# sensact_eagle_2_0g.net
KiCad netlist of a schematic drawn in EAGLE
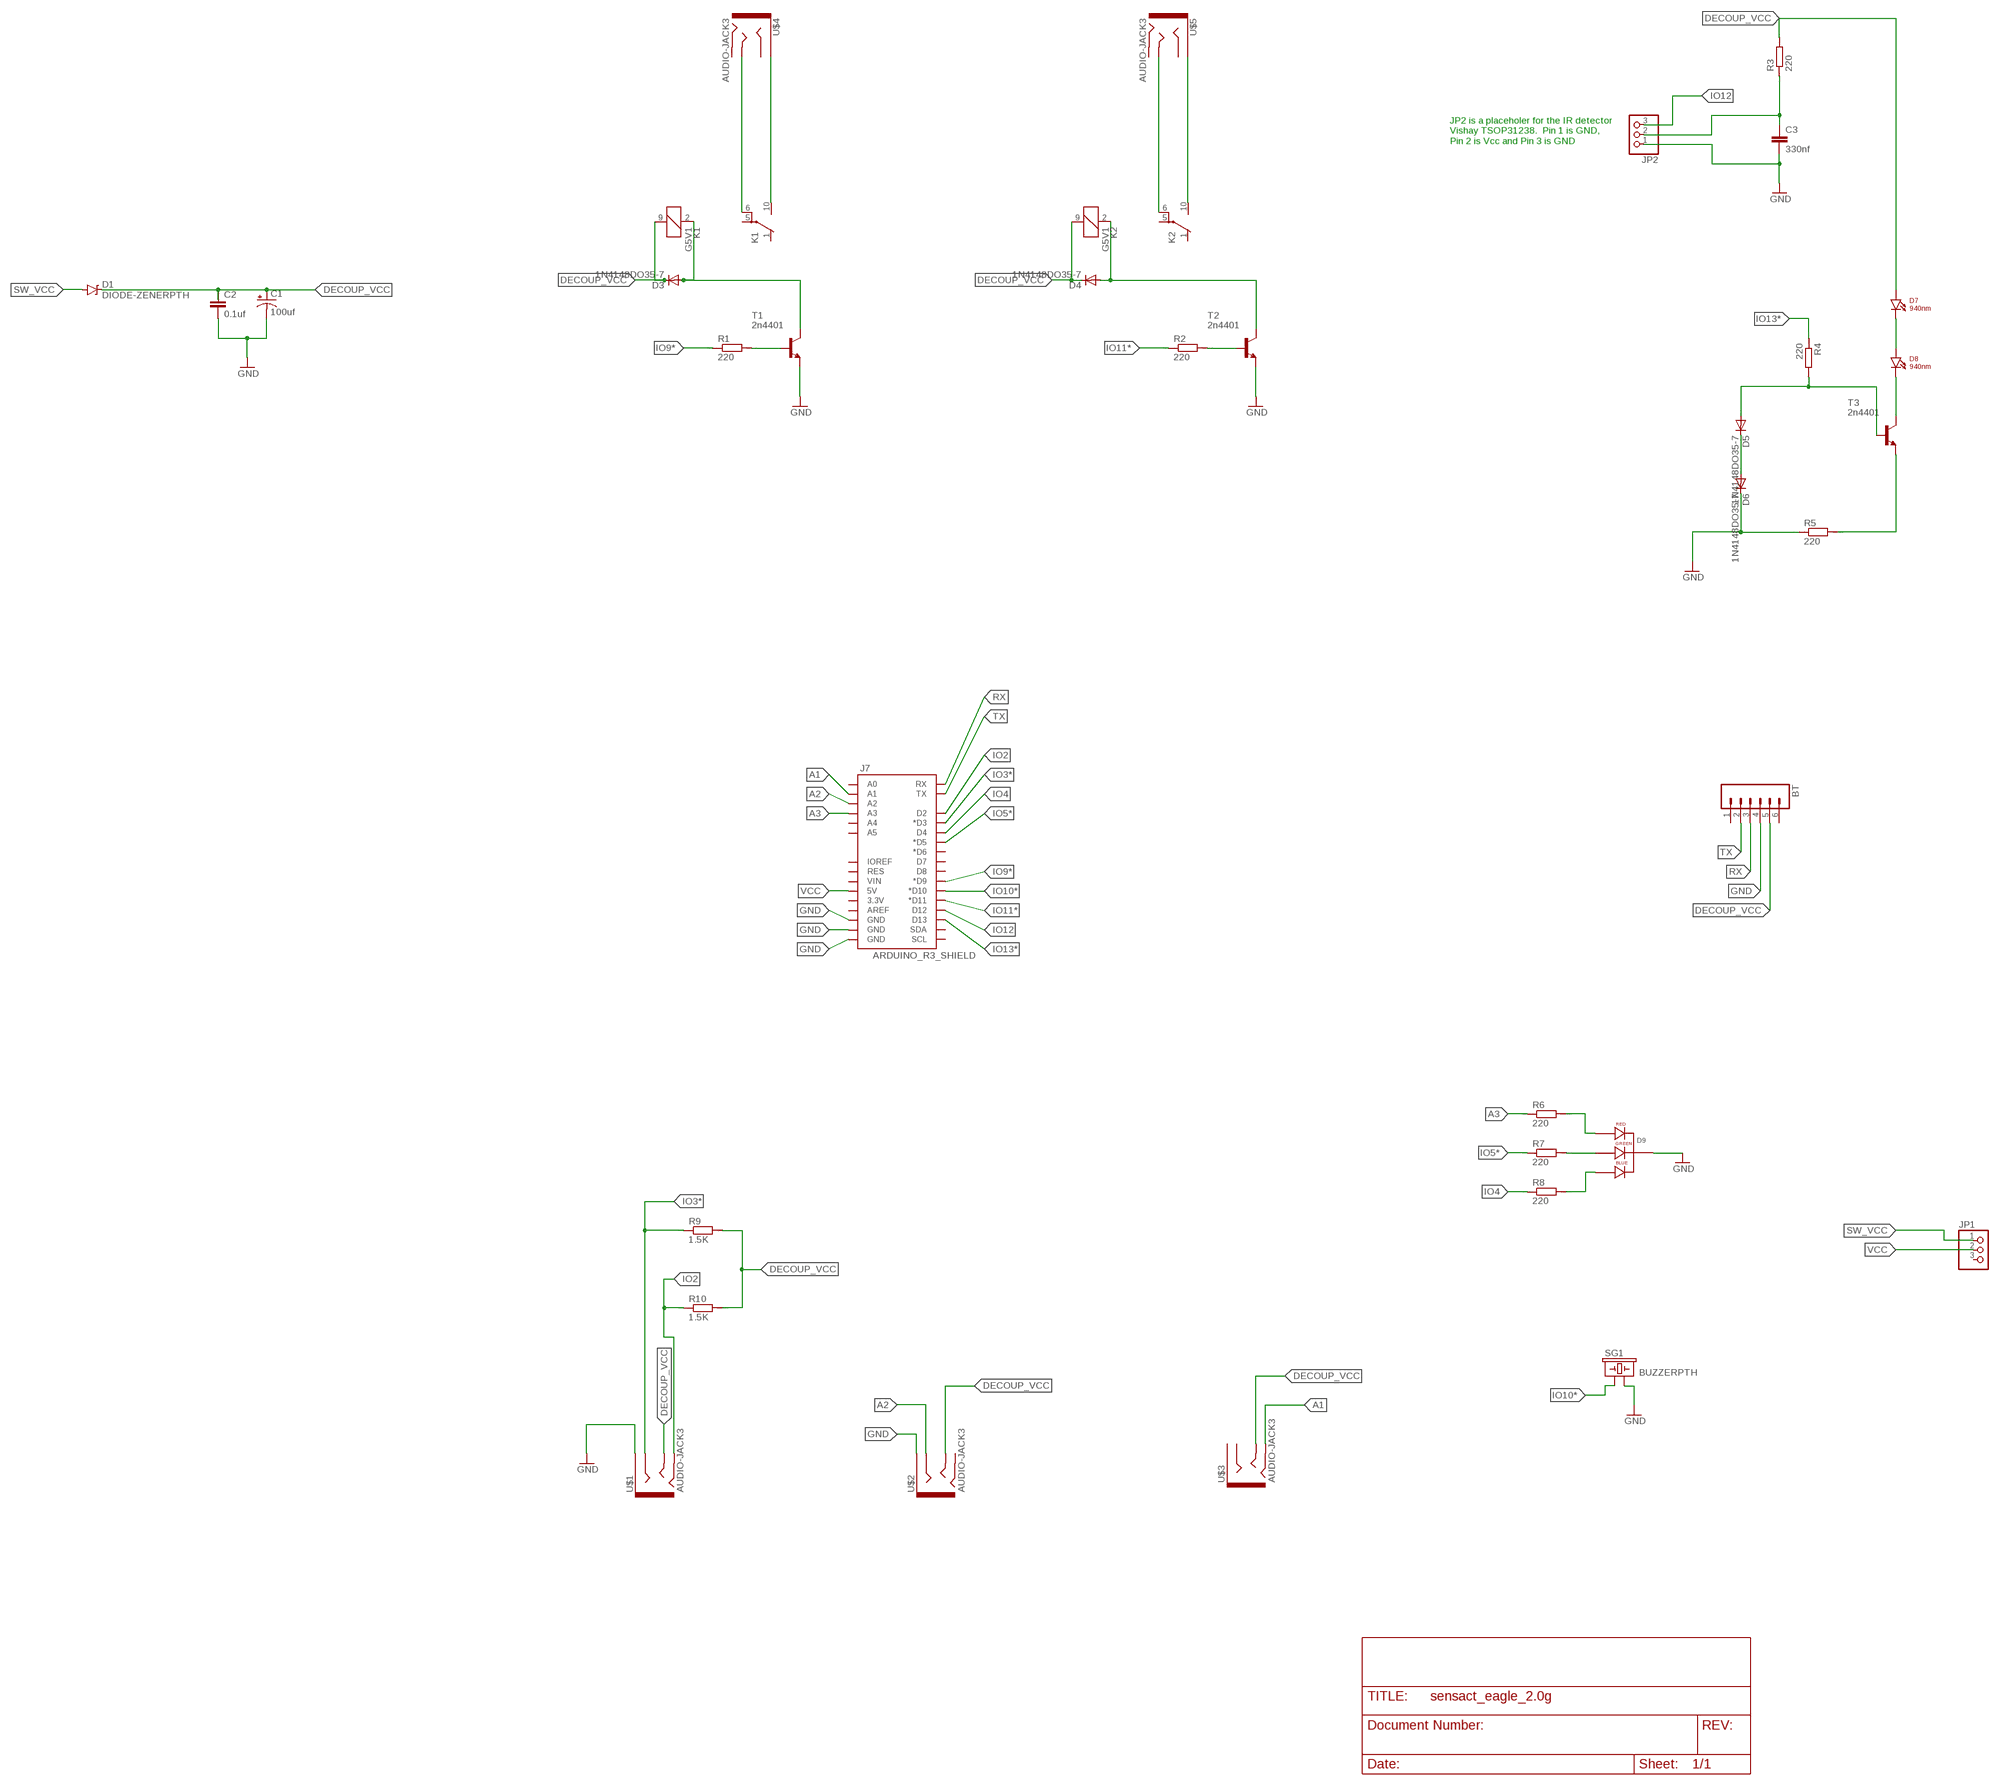
[diagram p0: schematic, sheet 1]

(export (version "E")
  (design (tool "Eeschema 10.0.6"))
  (components
    (comp (ref "BT")
      (value "M06NO_SILK_FEMALE_PTH")
      (footprint "eagle-import:1X06_NO_SILK")
      (libsource (lib "eagle-import") (part "M06NO_SILK_FEMALE_PTH"))
    )
    (comp (ref "C1")
      (value "100uf")
      (footprint "eagle-import:CPOL-RADIAL-100UF-25V")
      (libsource (lib "eagle-import") (part "CAP_POLPTH1"))
    )
    (comp (ref "C2")
      (value "0.1uf")
      (footprint "eagle-import:CAP-PTH-SMALLEZ")
      (libsource (lib "eagle-import") (part "CAPEZ"))
    )
    (comp (ref "C3")
      (value "330nf")
      (footprint "eagle-import:CAP-PTH-SMALLEZ")
      (libsource (lib "eagle-import") (part "CAPEZ"))
    )
    (comp (ref "D1")
      (value "DIODE-ZENERPTH")
      (footprint "eagle-import:DIODE-ZENER")
      (libsource (lib "eagle-import") (part "DIODE-ZENERPTH"))
    )
    (comp (ref "D3")
      (value "1N4148DO35-7")
      (footprint "eagle-import:DO35-7")
      (libsource (lib "eagle-import") (part "1N4148DO35-7"))
    )
    (comp (ref "D4")
      (value "1N4148DO35-7")
      (footprint "eagle-import:DO35-7")
      (libsource (lib "eagle-import") (part "1N4148DO35-7"))
    )
    (comp (ref "D5")
      (value "1N4148DO35-7")
      (footprint "eagle-import:DO35-7")
      (libsource (lib "eagle-import") (part "1N4148DO35-7"))
    )
    (comp (ref "D6")
      (value "1N4148DO35-7")
      (footprint "eagle-import:DO35-7")
      (libsource (lib "eagle-import") (part "1N4148DO35-7"))
    )
    (comp (ref "D7")
      (value "940nm")
      (footprint "eagle-import:LTE-302")
      (libsource (lib "eagle-import") (part "LTE-302"))
    )
    (comp (ref "D8")
      (value "940nm")
      (footprint "eagle-import:LTE-302")
      (libsource (lib "eagle-import") (part "LTE-302"))
    )
    (comp (ref "D9")
      (value "OFFSET_RGB_LED_CCOFFSET_RGB_LED_THRU")
      (footprint "eagle-import:OFFSET_RGB_THRU")
      (libsource (lib "eagle-import") (part "OFFSET_RGB_LED_CCOFFSET_RGB_LED_THRU"))
    )
    (comp (ref "J7")
      (value "ARDUINO_R3_SHIELD")
      (footprint "eagle-import:UNO_R3_SHIELD")
      (libsource (lib "eagle-import") (part "ARDUINO_R3_SHIELD"))
    )
    (comp (ref "JP1")
      (value "PINHD-1X3")
      (footprint "eagle-import:1X03")
      (libsource (lib "eagle-import") (part "PINHD-1X3"))
    )
    (comp (ref "JP2")
      (value "PINHD-1X3")
      (footprint "eagle-import:1X03")
      (libsource (lib "eagle-import") (part "PINHD-1X3"))
    )
    (comp (ref "K1")
      (value "G5V1")
      (footprint "eagle-import:G5V1")
      (fields (field (name "MPN") "G5V-1-DC24"))
      (libsource (lib "eagle-import") (part "G5V1"))
    )
    (comp (ref "K2")
      (value "G5V1")
      (footprint "eagle-import:G5V1")
      (fields (field (name "MPN") "G5V-1-DC24"))
      (libsource (lib "eagle-import") (part "G5V1"))
    )
    (comp (ref "R1")
      (value "220")
      (footprint "eagle-import:0204_7")
      (libsource (lib "eagle-import") (part "R0204/7"))
    )
    (comp (ref "R2")
      (value "220")
      (footprint "eagle-import:0204_7")
      (libsource (lib "eagle-import") (part "R0204/7"))
    )
    (comp (ref "R3")
      (value "220")
      (footprint "eagle-import:0204_7")
      (libsource (lib "eagle-import") (part "R0204/7"))
    )
    (comp (ref "R4")
      (value "220")
      (footprint "eagle-import:0204_7")
      (libsource (lib "eagle-import") (part "R0204/7"))
    )
    (comp (ref "R5")
      (value "220")
      (footprint "eagle-import:0204_7")
      (libsource (lib "eagle-import") (part "R0204/7"))
    )
    (comp (ref "R6")
      (value "220")
      (footprint "eagle-import:0204_7")
      (libsource (lib "eagle-import") (part "R0204/7"))
    )
    (comp (ref "R7")
      (value "220")
      (footprint "eagle-import:0204_7")
      (libsource (lib "eagle-import") (part "R0204/7"))
    )
    (comp (ref "R8")
      (value "220")
      (footprint "eagle-import:0204_7")
      (libsource (lib "eagle-import") (part "R0204/7"))
    )
    (comp (ref "R9")
      (value "1.5K")
      (footprint "eagle-import:0204_7")
      (libsource (lib "eagle-import") (part "R0204/7"))
    )
    (comp (ref "R10")
      (value "1.5K")
      (footprint "eagle-import:0204_7")
      (libsource (lib "eagle-import") (part "R0204/7"))
    )
    (comp (ref "SG1")
      (value "BUZZERPTH")
      (footprint "eagle-import:BUZZER-12MM")
      (libsource (lib "eagle-import") (part "BUZZERPTH"))
    )
    (comp (ref "T1")
      (value "2n4401")
      (footprint "eagle-import:TO92-EBC")
      (libsource (lib "eagle-import") (part "-NPN-TO92-EBC2N4401"))
    )
    (comp (ref "T2")
      (value "2n4401")
      (footprint "eagle-import:TO92-EBC")
      (libsource (lib "eagle-import") (part "-NPN-TO92-EBC2N4401"))
    )
    (comp (ref "T3")
      (value "2n4401")
      (footprint "eagle-import:TO92-EBC")
      (libsource (lib "eagle-import") (part "-NPN-TO92-EBC2N4401"))
    )
    (comp (ref "U$1")
      (value "AUDIO-JACK3")
      (footprint "eagle-import:AUDIO-JACK-TRRS-SMD")
      (libsource (lib "eagle-import") (part "AUDIO-JACK3"))
    )
    (comp (ref "U$2")
      (value "AUDIO-JACK3")
      (footprint "eagle-import:AUDIO-JACK-TRRS-SMD")
      (libsource (lib "eagle-import") (part "AUDIO-JACK3"))
    )
    (comp (ref "U$3")
      (value "AUDIO-JACK3")
      (footprint "eagle-import:AUDIO-JACK-TRRS-SMD")
      (libsource (lib "eagle-import") (part "AUDIO-JACK3"))
    )
    (comp (ref "U$4")
      (value "AUDIO-JACK3")
      (footprint "eagle-import:AUDIO-JACK-TRRS-SMD")
      (libsource (lib "eagle-import") (part "AUDIO-JACK3"))
    )
    (comp (ref "U$5")
      (value "AUDIO-JACK3")
      (footprint "eagle-import:AUDIO-JACK-TRRS-SMD")
      (libsource (lib "eagle-import") (part "AUDIO-JACK3"))
    )
  )
  (nets
    (net (code "1") (name "A1") (class "Default")
      (node (ref "J7") (pin "A1") (pinfunction "A1_A1") (pintype "bidirectional"))
      (node (ref "U$3") (pin "RING2") (pinfunction "RING2_RING2") (pintype "bidirectional"))
    )
    (net (code "2") (name "A2") (class "Default")
      (node (ref "J7") (pin "A2") (pinfunction "A2_A2") (pintype "bidirectional"))
      (node (ref "U$2") (pin "RING1") (pinfunction "RING1_RING1") (pintype "bidirectional"))
    )
    (net (code "3") (name "A3") (class "Default")
      (node (ref "J7") (pin "A3") (pinfunction "A3_A3") (pintype "bidirectional"))
      (node (ref "R6") (pin "1") (pinfunction "1_1") (pintype "passive"))
    )
    (net (code "4") (name "DECOUP_VCC") (class "Default")
      (node (ref "BT") (pin "5") (pinfunction "5_5") (pintype "passive"))
      (node (ref "C1") (pin "1") (pinfunction "+_1") (pintype "passive"))
      (node (ref "C2") (pin "1") (pinfunction "1_1") (pintype "passive"))
      (node (ref "D1") (pin "P$1") (pinfunction "C_P$1") (pintype "passive"))
      (node (ref "D3") (pin "C") (pinfunction "C_C") (pintype "passive"))
      (node (ref "D4") (pin "C") (pinfunction "C_C") (pintype "passive"))
      (node (ref "D7") (pin "A") (pinfunction "A_A") (pintype "bidirectional"))
      (node (ref "K1") (pin "9") (pinfunction "2_9") (pintype "passive"))
      (node (ref "K2") (pin "9") (pinfunction "2_9") (pintype "passive"))
      (node (ref "R10") (pin "2") (pinfunction "2_2") (pintype "passive"))
      (node (ref "R3") (pin "2") (pinfunction "2_2") (pintype "passive"))
      (node (ref "R9") (pin "2") (pinfunction "2_2") (pintype "passive"))
      (node (ref "U$1") (pin "TIP") (pinfunction "TIP_TIP") (pintype "bidirectional"))
      (node (ref "U$2") (pin "TIP") (pinfunction "TIP_TIP") (pintype "bidirectional"))
      (node (ref "U$3") (pin "TIP") (pinfunction "TIP_TIP") (pintype "bidirectional"))
    )
    (net (code "5") (name "GND") (class "Default")
      (node (ref "BT") (pin "4") (pinfunction "4_4") (pintype "passive"))
      (node (ref "C1") (pin "2") (pinfunction "-_2") (pintype "passive"))
      (node (ref "C2") (pin "2") (pinfunction "2_2") (pintype "passive"))
      (node (ref "C3") (pin "2") (pinfunction "2_2") (pintype "passive"))
      (node (ref "D6") (pin "C") (pinfunction "C_C") (pintype "passive"))
      (node (ref "D9") (pin "2") (pinfunction "CATHODE_2") (pintype "bidirectional"))
      (node (ref "J7") (pin "GND@0") (pinfunction "GND_GND@0") (pintype "bidirectional"))
      (node (ref "J7") (pin "GND@1") (pinfunction "GND_GND@1") (pintype "bidirectional"))
      (node (ref "J7") (pin "GND@2") (pinfunction "GND_GND@2") (pintype "bidirectional"))
      (node (ref "JP2") (pin "1") (pinfunction "1_1") (pintype "passive"))
      (node (ref "R5") (pin "1") (pinfunction "1_1") (pintype "passive"))
      (node (ref "SG1") (pin "-") (pinfunction "2_-") (pintype "passive"))
      (node (ref "T1") (pin "E") (pinfunction "E_E") (pintype "passive"))
      (node (ref "T2") (pin "E") (pinfunction "E_E") (pintype "passive"))
      (node (ref "U$1") (pin "EARTH") (pinfunction "EARTH_EARTH") (pintype "bidirectional"))
      (node (ref "U$2") (pin "EARTH") (pinfunction "EARTH_EARTH") (pintype "bidirectional"))
    )
    (net (code "6") (name "IO2") (class "Default")
      (node (ref "J7") (pin "D2") (pinfunction "D2_D2") (pintype "bidirectional"))
      (node (ref "R10") (pin "1") (pinfunction "1_1") (pintype "passive"))
      (node (ref "U$1") (pin "RING2") (pinfunction "RING2_RING2") (pintype "bidirectional"))
    )
    (net (code "7") (name "IO3*") (class "Default")
      (node (ref "J7") (pin "D3") (pinfunction "*D3_D3") (pintype "bidirectional"))
      (node (ref "R9") (pin "1") (pinfunction "1_1") (pintype "passive"))
      (node (ref "U$1") (pin "RING1") (pinfunction "RING1_RING1") (pintype "bidirectional"))
    )
    (net (code "8") (name "IO4") (class "Default")
      (node (ref "J7") (pin "D4") (pinfunction "D4_D4") (pintype "bidirectional"))
      (node (ref "R8") (pin "1") (pinfunction "1_1") (pintype "passive"))
    )
    (net (code "9") (name "IO5*") (class "Default")
      (node (ref "J7") (pin "D5") (pinfunction "*D5_D5") (pintype "bidirectional"))
      (node (ref "R7") (pin "1") (pinfunction "1_1") (pintype "passive"))
    )
    (net (code "10") (name "IO9*") (class "Default")
      (node (ref "J7") (pin "D9") (pinfunction "*D9_D9") (pintype "bidirectional"))
      (node (ref "R1") (pin "1") (pinfunction "1_1") (pintype "passive"))
    )
    (net (code "11") (name "IO10*") (class "Default")
      (node (ref "J7") (pin "D10") (pinfunction "*D10_D10") (pintype "bidirectional"))
      (node (ref "SG1") (pin "+") (pinfunction "1_+") (pintype "passive"))
    )
    (net (code "12") (name "IO11*") (class "Default")
      (node (ref "J7") (pin "D11") (pinfunction "*D11_D11") (pintype "bidirectional"))
      (node (ref "R2") (pin "1") (pinfunction "1_1") (pintype "passive"))
    )
    (net (code "13") (name "IO12") (class "Default")
      (node (ref "J7") (pin "D12") (pinfunction "D12_D12") (pintype "bidirectional"))
      (node (ref "JP2") (pin "3") (pinfunction "3_3") (pintype "passive"))
    )
    (net (code "14") (name "IO13*") (class "Default")
      (node (ref "J7") (pin "D13") (pinfunction "D13_D13") (pintype "bidirectional"))
      (node (ref "R4") (pin "1") (pinfunction "1_1") (pintype "passive"))
    )
    (net (code "15") (name "Net-(C3-Pad1)") (class "Default")
      (node (ref "C3") (pin "1") (pinfunction "1_1") (pintype "passive"))
      (node (ref "JP2") (pin "2") (pinfunction "2_2") (pintype "passive"))
      (node (ref "R3") (pin "1") (pinfunction "1_1") (pintype "passive"))
    )
    (net (code "16") (name "Net-(D5-PadA)") (class "Default")
      (node (ref "D5") (pin "A") (pinfunction "A_A") (pintype "passive"))
      (node (ref "R4") (pin "2") (pinfunction "2_2") (pintype "passive"))
      (node (ref "T3") (pin "B") (pinfunction "B_B") (pintype "passive"))
    )
    (net (code "17") (name "Net-(D5-PadC)") (class "Default")
      (node (ref "D5") (pin "C") (pinfunction "C_C") (pintype "passive"))
      (node (ref "D6") (pin "A") (pinfunction "A_A") (pintype "passive"))
    )
    (net (code "18") (name "Net-(D7-PadC)") (class "Default")
      (node (ref "D7") (pin "C") (pinfunction "C_C") (pintype "bidirectional"))
      (node (ref "D8") (pin "A") (pinfunction "A_A") (pintype "bidirectional"))
    )
    (net (code "19") (name "Net-(D8-PadC)") (class "Default")
      (node (ref "D8") (pin "C") (pinfunction "C_C") (pintype "bidirectional"))
      (node (ref "T3") (pin "C") (pinfunction "C_C") (pintype "passive"))
    )
    (net (code "20") (name "Net-(D9-BLUE_CATHODE)") (class "Default")
      (node (ref "D9") (pin "4") (pinfunction "BLUE_CATHODE_4") (pintype "bidirectional"))
      (node (ref "R8") (pin "2") (pinfunction "2_2") (pintype "passive"))
    )
    (net (code "21") (name "Net-(D9-GREEN_CATHODE)") (class "Default")
      (node (ref "D9") (pin "3") (pinfunction "GREEN_CATHODE_3") (pintype "bidirectional"))
      (node (ref "R7") (pin "2") (pinfunction "2_2") (pintype "passive"))
    )
    (net (code "22") (name "Net-(D9-RED_CATHODE)") (class "Default")
      (node (ref "D9") (pin "1") (pinfunction "RED_CATHODE_1") (pintype "bidirectional"))
      (node (ref "R6") (pin "2") (pinfunction "2_2") (pintype "passive"))
    )
    (net (code "23") (name "Net-(K1A-1)") (class "Default")
      (node (ref "D3") (pin "A") (pinfunction "A_A") (pintype "passive"))
      (node (ref "K1") (pin "2") (pinfunction "1_2") (pintype "passive"))
      (node (ref "T1") (pin "C") (pinfunction "C_C") (pintype "passive"))
    )
    (net (code "24") (name "Net-(K1B-P-Pad6)") (class "Default")
      (node (ref "K1") (pin "6") (pinfunction "P_6") (pintype "passive"))
      (node (ref "U$4") (pin "TIP") (pinfunction "TIP_TIP") (pintype "bidirectional"))
    )
    (net (code "25") (name "Net-(K1B-S)") (class "Default")
      (node (ref "K1") (pin "10") (pinfunction "S_10") (pintype "passive"))
      (node (ref "U$4") (pin "EARTH") (pinfunction "EARTH_EARTH") (pintype "bidirectional"))
    )
    (net (code "26") (name "Net-(K2A-1)") (class "Default")
      (node (ref "D4") (pin "A") (pinfunction "A_A") (pintype "passive"))
      (node (ref "K2") (pin "2") (pinfunction "1_2") (pintype "passive"))
      (node (ref "T2") (pin "C") (pinfunction "C_C") (pintype "passive"))
    )
    (net (code "27") (name "Net-(K2B-P-Pad6)") (class "Default")
      (node (ref "K2") (pin "6") (pinfunction "P_6") (pintype "passive"))
      (node (ref "U$5") (pin "TIP") (pinfunction "TIP_TIP") (pintype "bidirectional"))
    )
    (net (code "28") (name "Net-(K2B-S)") (class "Default")
      (node (ref "K2") (pin "10") (pinfunction "S_10") (pintype "passive"))
      (node (ref "U$5") (pin "EARTH") (pinfunction "EARTH_EARTH") (pintype "bidirectional"))
    )
    (net (code "29") (name "Net-(R1-Pad2)") (class "Default")
      (node (ref "R1") (pin "2") (pinfunction "2_2") (pintype "passive"))
      (node (ref "T1") (pin "B") (pinfunction "B_B") (pintype "passive"))
    )
    (net (code "30") (name "Net-(R2-Pad2)") (class "Default")
      (node (ref "R2") (pin "2") (pinfunction "2_2") (pintype "passive"))
      (node (ref "T2") (pin "B") (pinfunction "B_B") (pintype "passive"))
    )
    (net (code "31") (name "Net-(R5-Pad2)") (class "Default")
      (node (ref "R5") (pin "2") (pinfunction "2_2") (pintype "passive"))
      (node (ref "T3") (pin "E") (pinfunction "E_E") (pintype "passive"))
    )
    (net (code "32") (name "RX") (class "Default")
      (node (ref "BT") (pin "3") (pinfunction "3_3") (pintype "passive"))
      (node (ref "J7") (pin "RX") (pinfunction "RX_RX") (pintype "bidirectional"))
    )
    (net (code "33") (name "SW_VCC") (class "Default")
      (node (ref "D1") (pin "P$2") (pinfunction "A_P$2") (pintype "passive"))
      (node (ref "JP1") (pin "1") (pinfunction "1_1") (pintype "passive"))
    )
    (net (code "34") (name "TX") (class "Default")
      (node (ref "BT") (pin "2") (pinfunction "2_2") (pintype "passive"))
      (node (ref "J7") (pin "TX") (pinfunction "TX_TX") (pintype "bidirectional"))
    )
    (net (code "35") (name "VCC") (class "Default")
      (node (ref "J7") (pin "5V") (pinfunction "5V_5V") (pintype "bidirectional"))
      (node (ref "JP1") (pin "2") (pinfunction "2_2") (pintype "passive"))
    )
    (net (code "36") (name "unconnected-(BT-Pad1)") (class "Default")
      (node (ref "BT") (pin "1") (pinfunction "1_1") (pintype "passive"))
    )
    (net (code "37") (name "unconnected-(BT-Pad6)") (class "Default")
      (node (ref "BT") (pin "6") (pinfunction "6_6") (pintype "passive"))
    )
    (net (code "38") (name "unconnected-(J7-*D6-PadD6)") (class "Default")
      (node (ref "J7") (pin "D6") (pinfunction "*D6_D6") (pintype "bidirectional"))
    )
    (net (code "39") (name "unconnected-(J7-Pad3.3V)") (class "Default")
      (node (ref "J7") (pin "3.3V") (pinfunction "3.3V_3.3V") (pintype "bidirectional"))
    )
    (net (code "40") (name "unconnected-(J7-PadA0)") (class "Default")
      (node (ref "J7") (pin "A0") (pinfunction "A0_A0") (pintype "bidirectional"))
    )
    (net (code "41") (name "unconnected-(J7-PadA4)") (class "Default")
      (node (ref "J7") (pin "A4") (pinfunction "A4_A4") (pintype "bidirectional"))
    )
    (net (code "42") (name "unconnected-(J7-PadA5)") (class "Default")
      (node (ref "J7") (pin "A5") (pinfunction "A5_A5") (pintype "bidirectional"))
    )
    (net (code "43") (name "unconnected-(J7-PadAREF)") (class "Default")
      (node (ref "J7") (pin "AREF") (pinfunction "AREF_AREF") (pintype "bidirectional"))
    )
    (net (code "44") (name "unconnected-(J7-PadD7)") (class "Default")
      (node (ref "J7") (pin "D7") (pinfunction "D7_D7") (pintype "bidirectional"))
    )
    (net (code "45") (name "unconnected-(J7-PadD8)") (class "Default")
      (node (ref "J7") (pin "D8") (pinfunction "D8_D8") (pintype "bidirectional"))
    )
    (net (code "46") (name "unconnected-(J7-PadIOREF)") (class "Default")
      (node (ref "J7") (pin "IOREF") (pinfunction "IOREF_IOREF") (pintype "bidirectional"))
    )
    (net (code "47") (name "unconnected-(J7-PadRES)") (class "Default")
      (node (ref "J7") (pin "RES") (pinfunction "RES_RES") (pintype "bidirectional"))
    )
    (net (code "48") (name "unconnected-(J7-PadSCL)") (class "Default")
      (node (ref "J7") (pin "SCL") (pinfunction "SCL_SCL") (pintype "bidirectional"))
    )
    (net (code "49") (name "unconnected-(J7-PadSDA)") (class "Default")
      (node (ref "J7") (pin "SDA") (pinfunction "SDA_SDA") (pintype "bidirectional"))
    )
    (net (code "50") (name "unconnected-(J7-PadVIN)") (class "Default")
      (node (ref "J7") (pin "VIN") (pinfunction "VIN_VIN") (pintype "bidirectional"))
    )
    (net (code "51") (name "unconnected-(JP1-Pad3)") (class "Default")
      (node (ref "JP1") (pin "3") (pinfunction "3_3") (pintype "passive"))
    )
    (net (code "52") (name "unconnected-(K1B-O-Pad1)") (class "Default")
      (node (ref "K1") (pin "1") (pinfunction "O_1") (pintype "passive"))
    )
    (net (code "53") (name "unconnected-(K1B-P-Pad5)") (class "Default")
      (node (ref "K1") (pin "5") (pinfunction "P_5") (pintype "passive"))
    )
    (net (code "54") (name "unconnected-(K2B-O-Pad1)") (class "Default")
      (node (ref "K2") (pin "1") (pinfunction "O_1") (pintype "passive"))
    )
    (net (code "55") (name "unconnected-(K2B-P-Pad5)") (class "Default")
      (node (ref "K2") (pin "5") (pinfunction "P_5") (pintype "passive"))
    )
    (net (code "56") (name "unconnected-(U$2-PadRING2)") (class "Default")
      (node (ref "U$2") (pin "RING2") (pinfunction "RING2_RING2") (pintype "bidirectional"))
    )
    (net (code "57") (name "unconnected-(U$3-PadEARTH)") (class "Default")
      (node (ref "U$3") (pin "EARTH") (pinfunction "EARTH_EARTH") (pintype "bidirectional"))
    )
    (net (code "58") (name "unconnected-(U$3-PadRING1)") (class "Default")
      (node (ref "U$3") (pin "RING1") (pinfunction "RING1_RING1") (pintype "bidirectional"))
    )
    (net (code "59") (name "unconnected-(U$4-PadRING1)") (class "Default")
      (node (ref "U$4") (pin "RING1") (pinfunction "RING1_RING1") (pintype "bidirectional"))
    )
    (net (code "60") (name "unconnected-(U$4-PadRING2)") (class "Default")
      (node (ref "U$4") (pin "RING2") (pinfunction "RING2_RING2") (pintype "bidirectional"))
    )
    (net (code "61") (name "unconnected-(U$5-PadRING1)") (class "Default")
      (node (ref "U$5") (pin "RING1") (pinfunction "RING1_RING1") (pintype "bidirectional"))
    )
    (net (code "62") (name "unconnected-(U$5-PadRING2)") (class "Default")
      (node (ref "U$5") (pin "RING2") (pinfunction "RING2_RING2") (pintype "bidirectional"))
    )
  )
)
